# schematic.net
KiCad netlist of a schematic drawn in EasyEDA
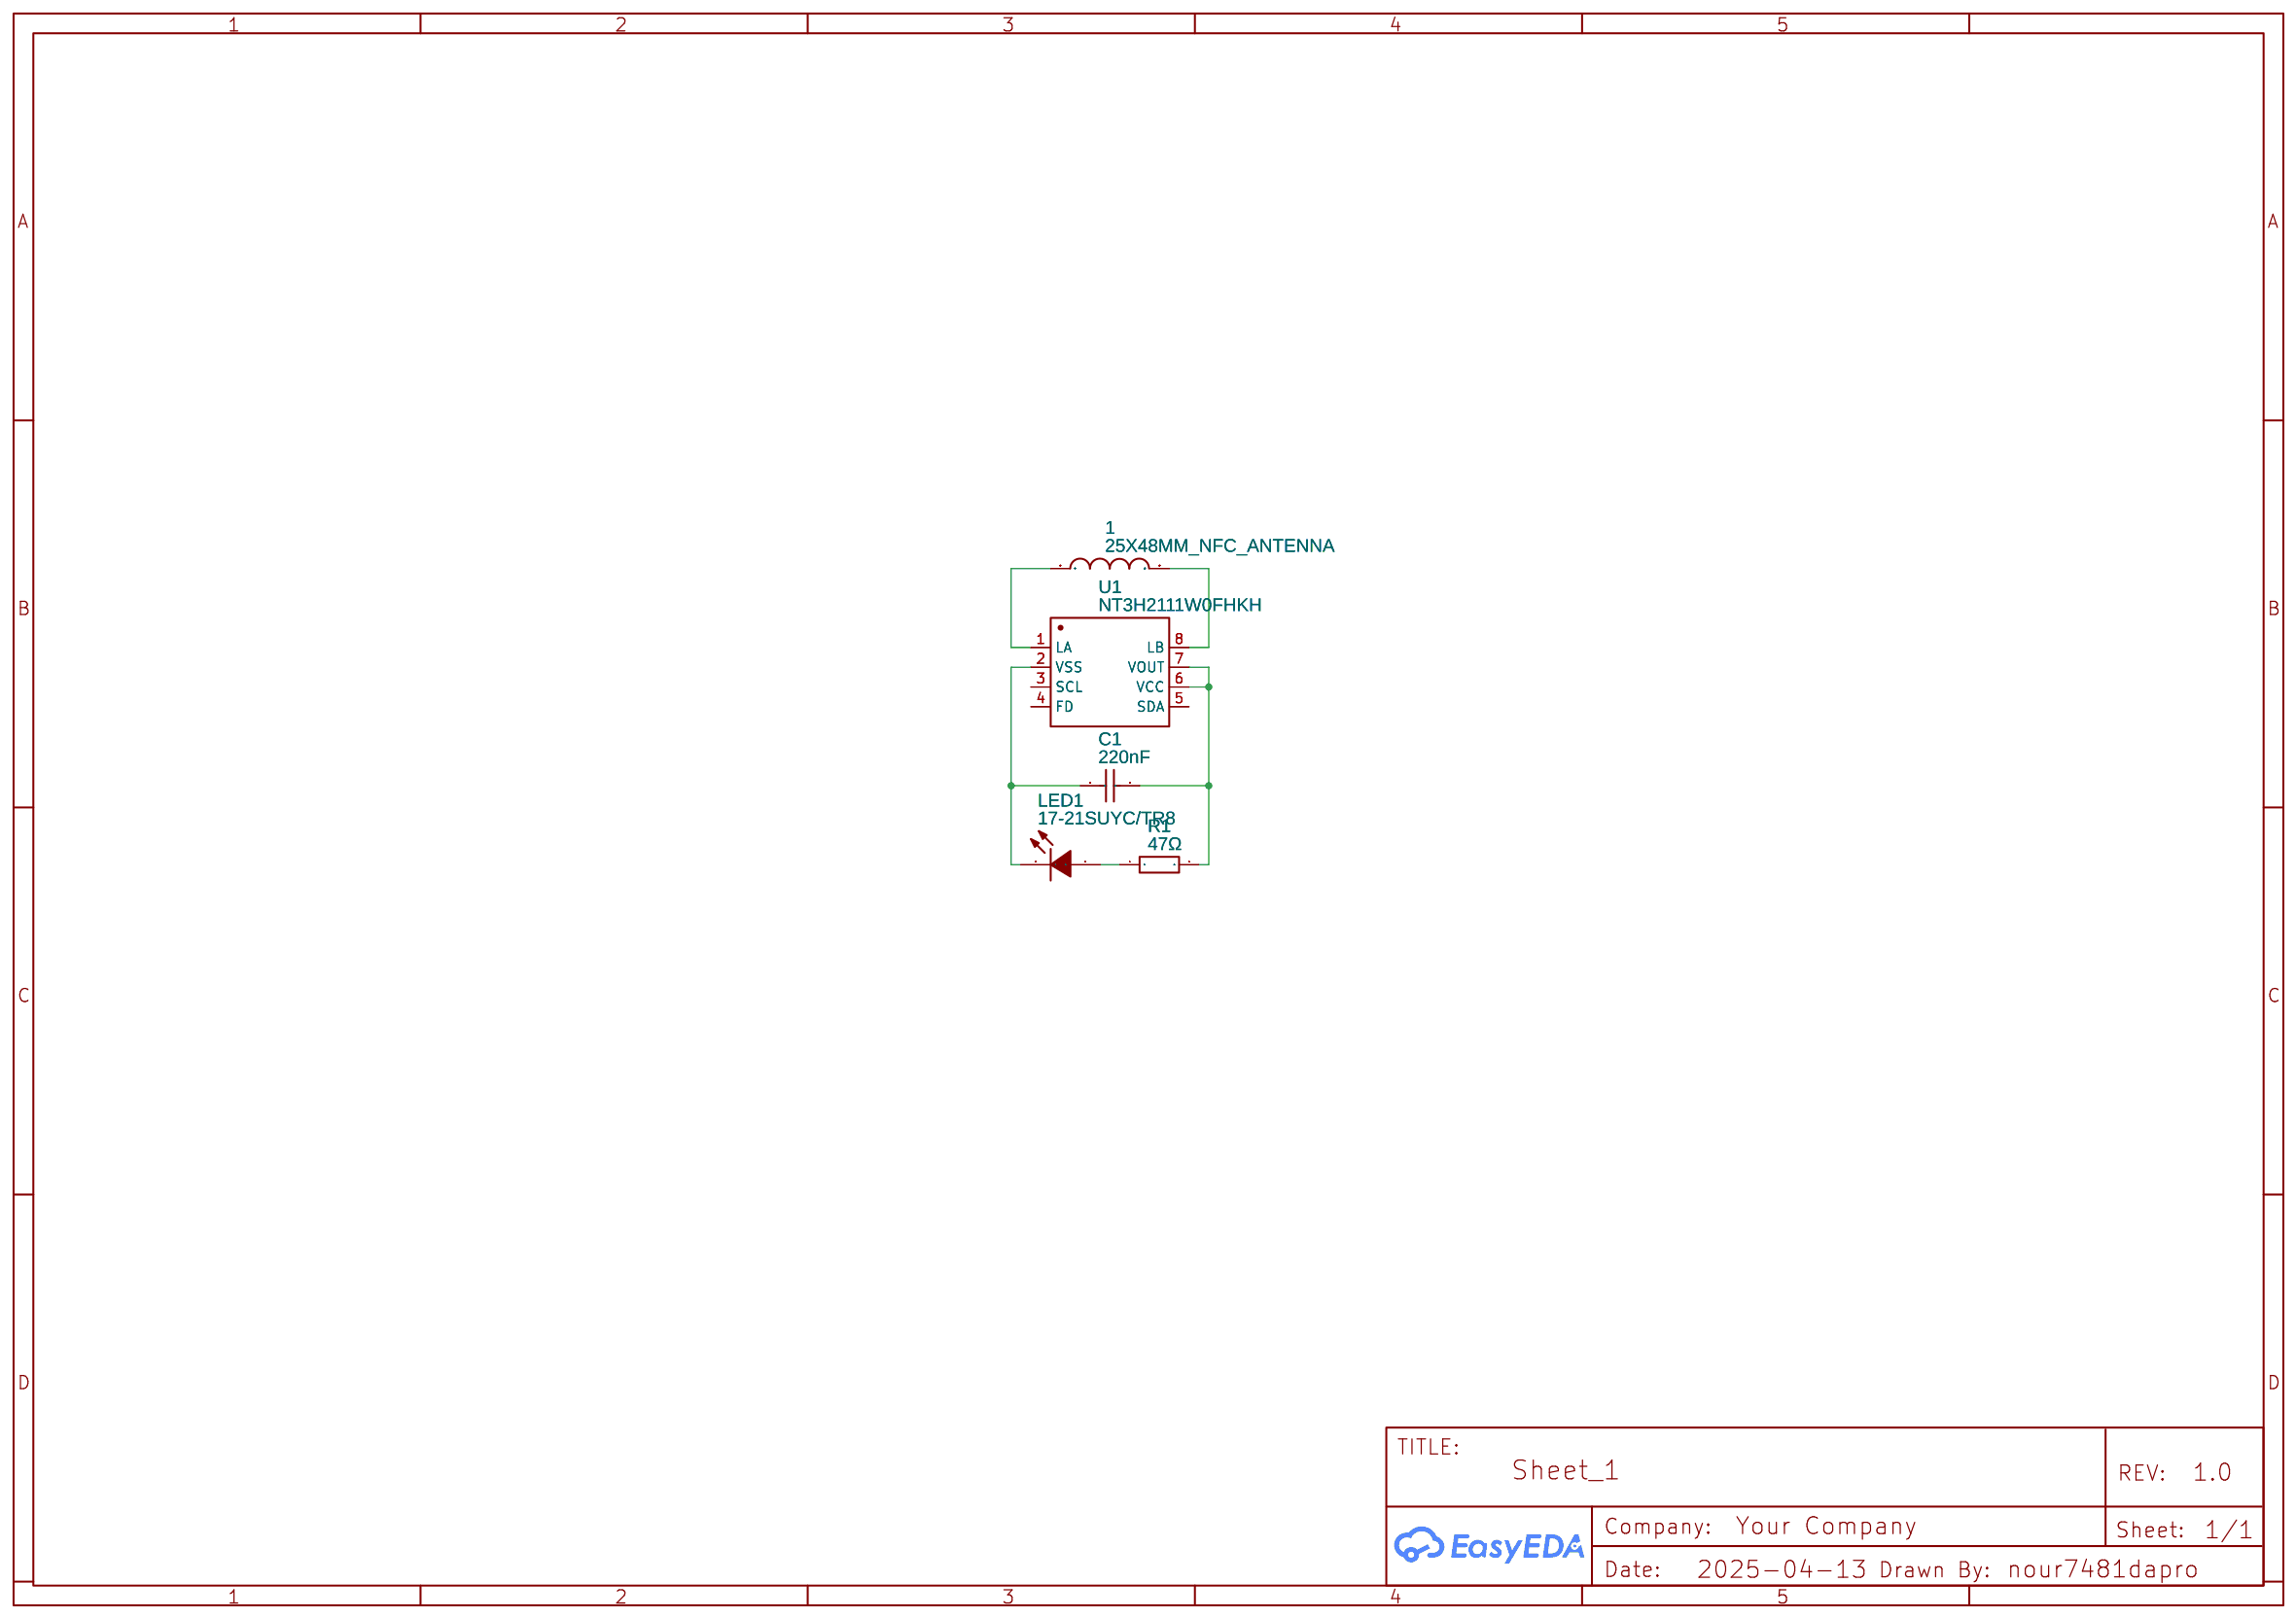
[diagram p0: schematic sheet]

(export (version "E")
  (design (tool "Eeschema 10.0.6"))
  (components
    (comp (ref "1") (value "25X48MM_NFC_ANTENNA") (libsource (lib "") (part "25X48MM_NFC_ANTENNA")))
    (comp (ref "C1")
      (value "220nF")
      (fields
        (field (name "Manufacturer Part") "CL10B224KB8NNNC")
        (field (name "Manufacturer") "SAMSUNG(三星)")
      )
      (libsource (lib "") (part "CL10B224KB8NNNC"))
    )
    (comp (ref "LED1")
      (value "17-21SUYC/TR8")
      (fields (field (name "Manufacturer Part") "KT-0805黄灯") (field (name "Manufacturer") "KENTO"))
      (libsource (lib "") (part "17-21SUYC/TR8"))
    )
    (comp (ref "R1")
      (value "47Ω")
      (fields
        (field (name "Manufacturer Part") "0603WAF470JT5E")
        (field (name "Manufacturer") "UNI-ROYAL(厚声)")
      )
      (libsource (lib "") (part "0603WAF470JT5E"))
    )
    (comp (ref "U1")
      (value "NT3H2111W0FHKH")
      (fields (field (name "Manufacturer") "NXP(恩智浦)"))
      (libsource (lib "") (part "NT3H2111W0FHKH"))
    )
  )
  (nets
    (net (code "1") (name "Net-(LED1-+)") (class "Default")
      (node (ref "LED1") (pin "1") (pinfunction "+_1") (pintype "unspecified"))
      (node (ref "R1") (pin "1") (pinfunction "1_1") (pintype "input"))
    )
    (net (code "2") (name "Net-(LED1--)") (class "Default")
      (node (ref "C1") (pin "1") (pinfunction "1_1") (pintype "input"))
      (node (ref "LED1") (pin "2") (pinfunction "-_2") (pintype "unspecified"))
      (node (ref "U1") (pin "2") (pinfunction "VSS_2") (pintype "unspecified"))
    )
    (net (code "3") (name "Net-(U1-LA)") (class "Default")
      (node (ref "1") (pin "P$1") (pinfunction "P$1_P$1") (pintype "bidirectional"))
      (node (ref "U1") (pin "1") (pinfunction "LA_1") (pintype "unspecified"))
    )
    (net (code "4") (name "Net-(U1-LB)") (class "Default")
      (node (ref "1") (pin "P$2") (pinfunction "P$2_P$2") (pintype "bidirectional"))
      (node (ref "U1") (pin "8") (pinfunction "LB_8") (pintype "unspecified"))
    )
    (net (code "5") (name "Net-(U1-VCC)") (class "Default")
      (node (ref "C1") (pin "2") (pinfunction "2_2") (pintype "input"))
      (node (ref "R1") (pin "2") (pinfunction "2_2") (pintype "input"))
      (node (ref "U1") (pin "6") (pinfunction "VCC_6") (pintype "unspecified"))
      (node (ref "U1") (pin "7") (pinfunction "VOUT_7") (pintype "unspecified"))
    )
    (net (code "6") (name "unconnected-(U1-FD-Pad4)") (class "Default")
      (node (ref "U1") (pin "4") (pinfunction "FD_4") (pintype "unspecified"))
    )
    (net (code "7") (name "unconnected-(U1-SCL-Pad3)") (class "Default")
      (node (ref "U1") (pin "3") (pinfunction "SCL_3") (pintype "unspecified"))
    )
    (net (code "8") (name "unconnected-(U1-SDA-Pad5)") (class "Default")
      (node (ref "U1") (pin "5") (pinfunction "SDA_5") (pintype "unspecified"))
    )
  )
)
